# 8ModuleBoard.net
KiCad netlist of a schematic drawn in EAGLE
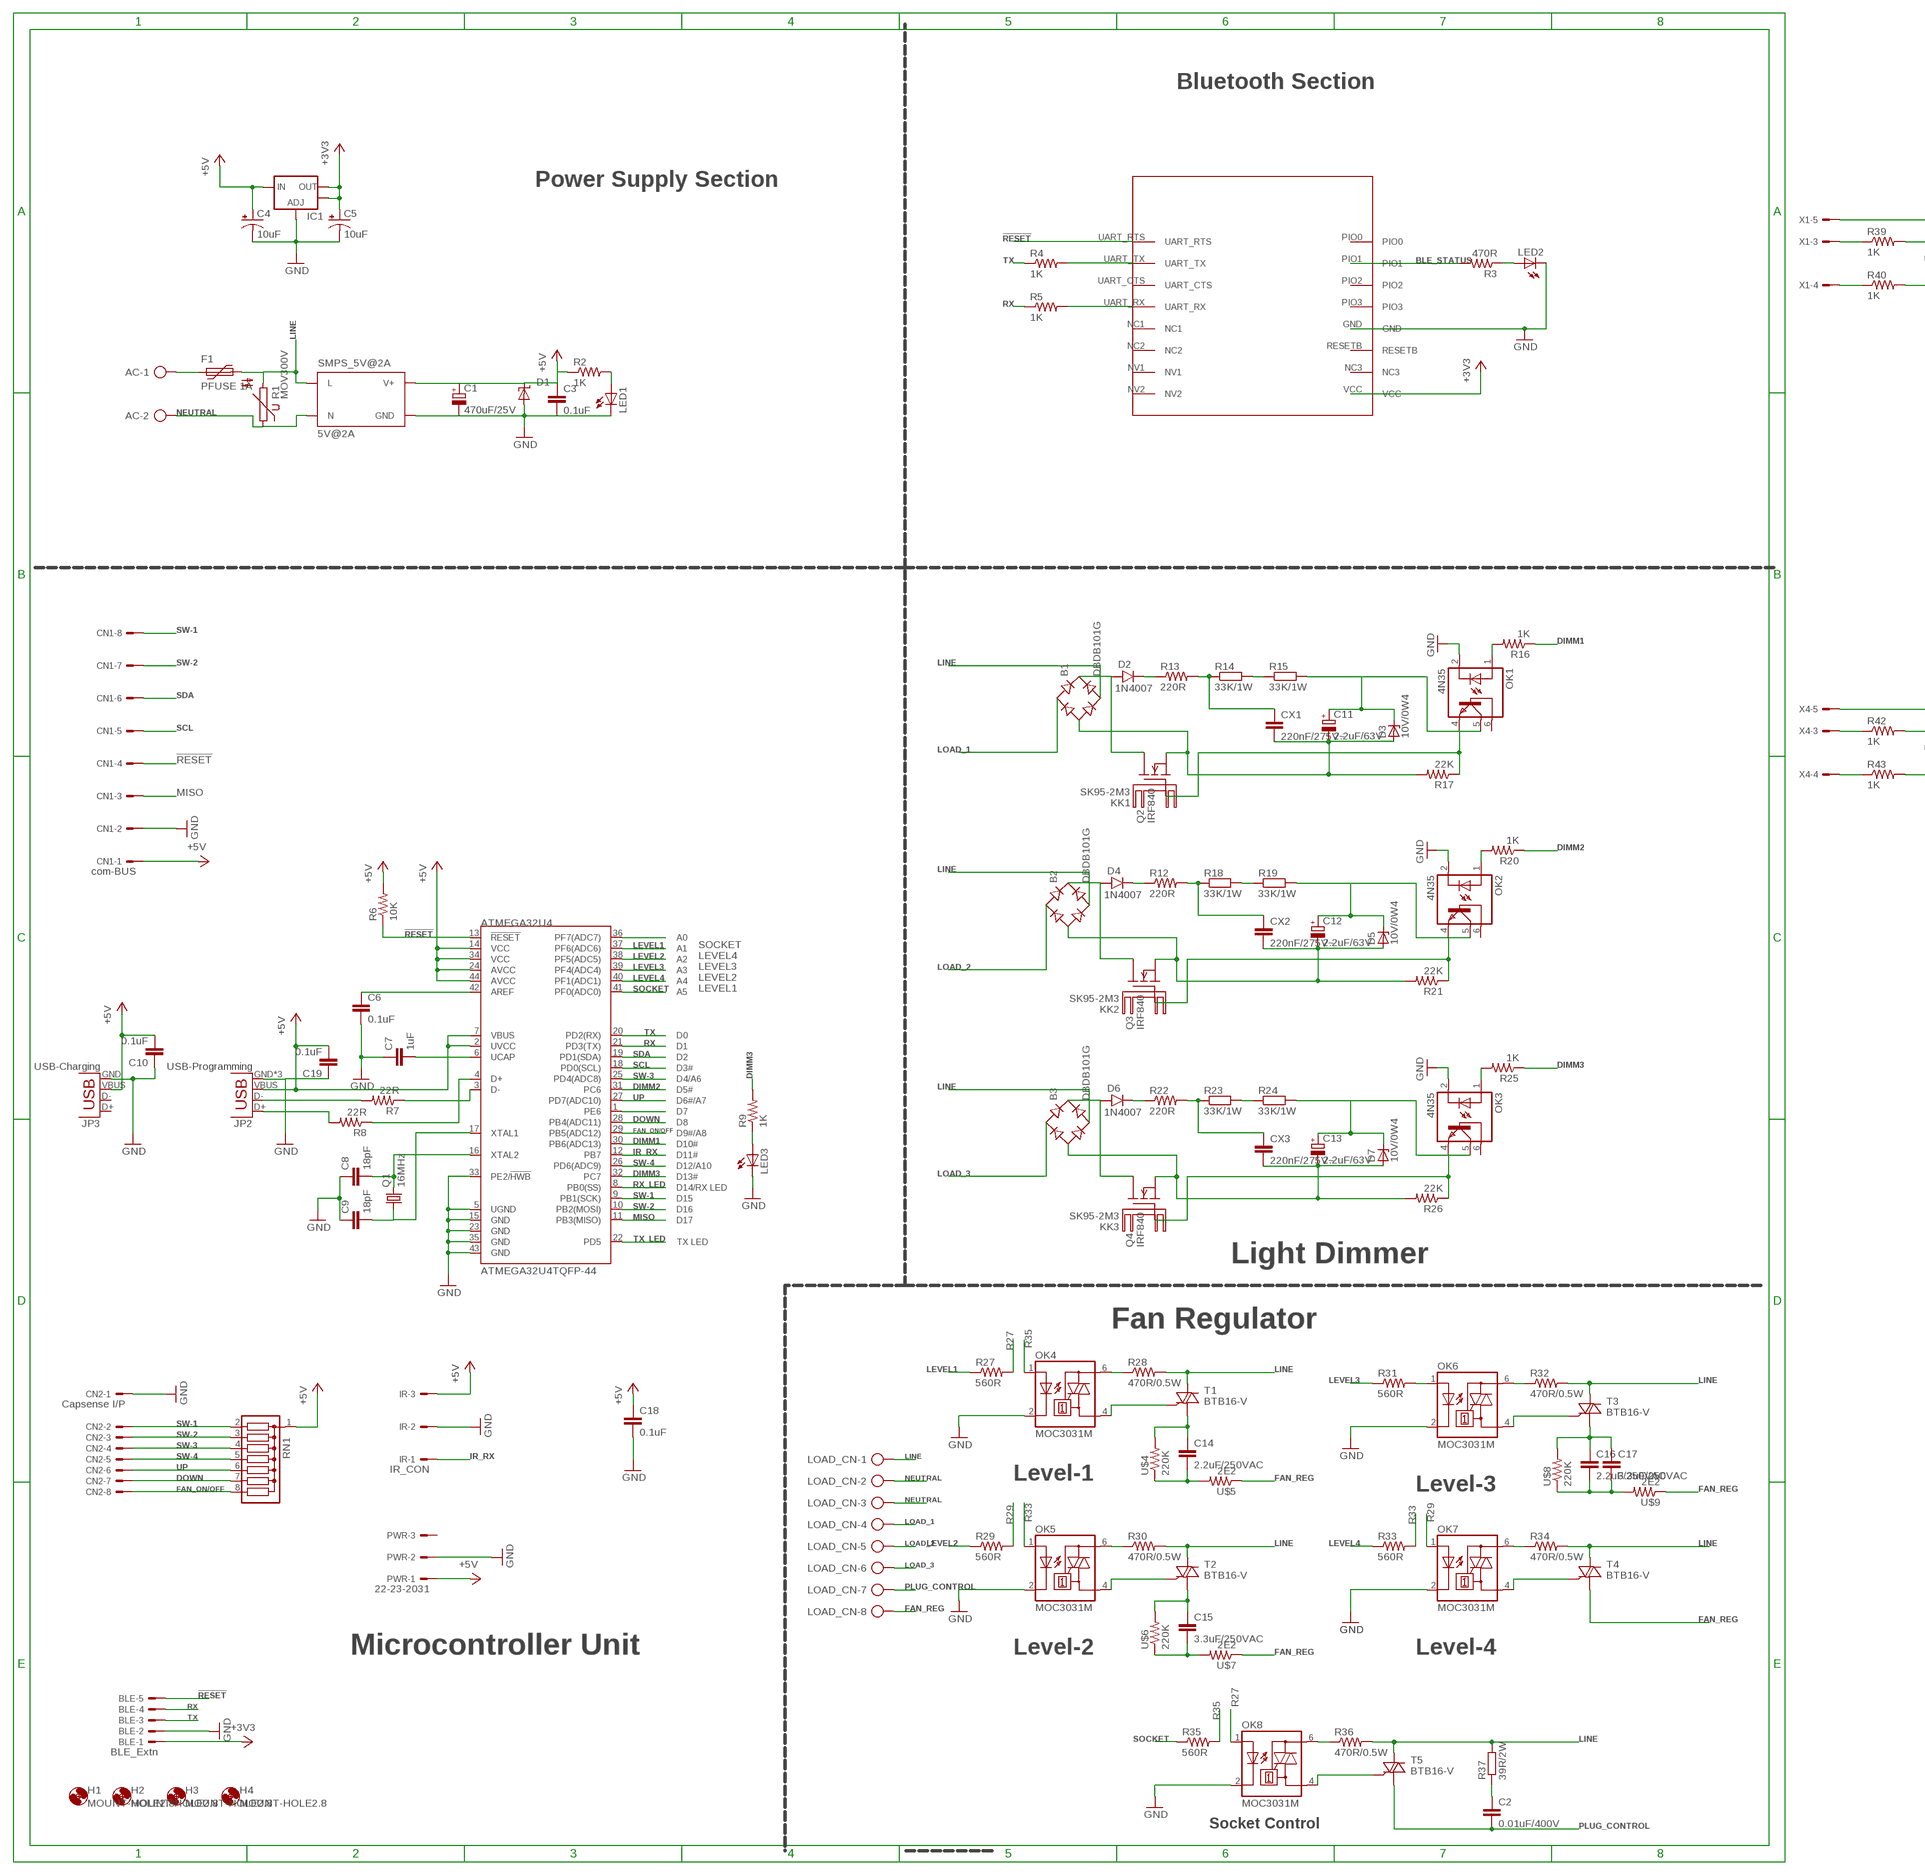
[diagram p0: schematic, sheet 1, part 1 of 2]
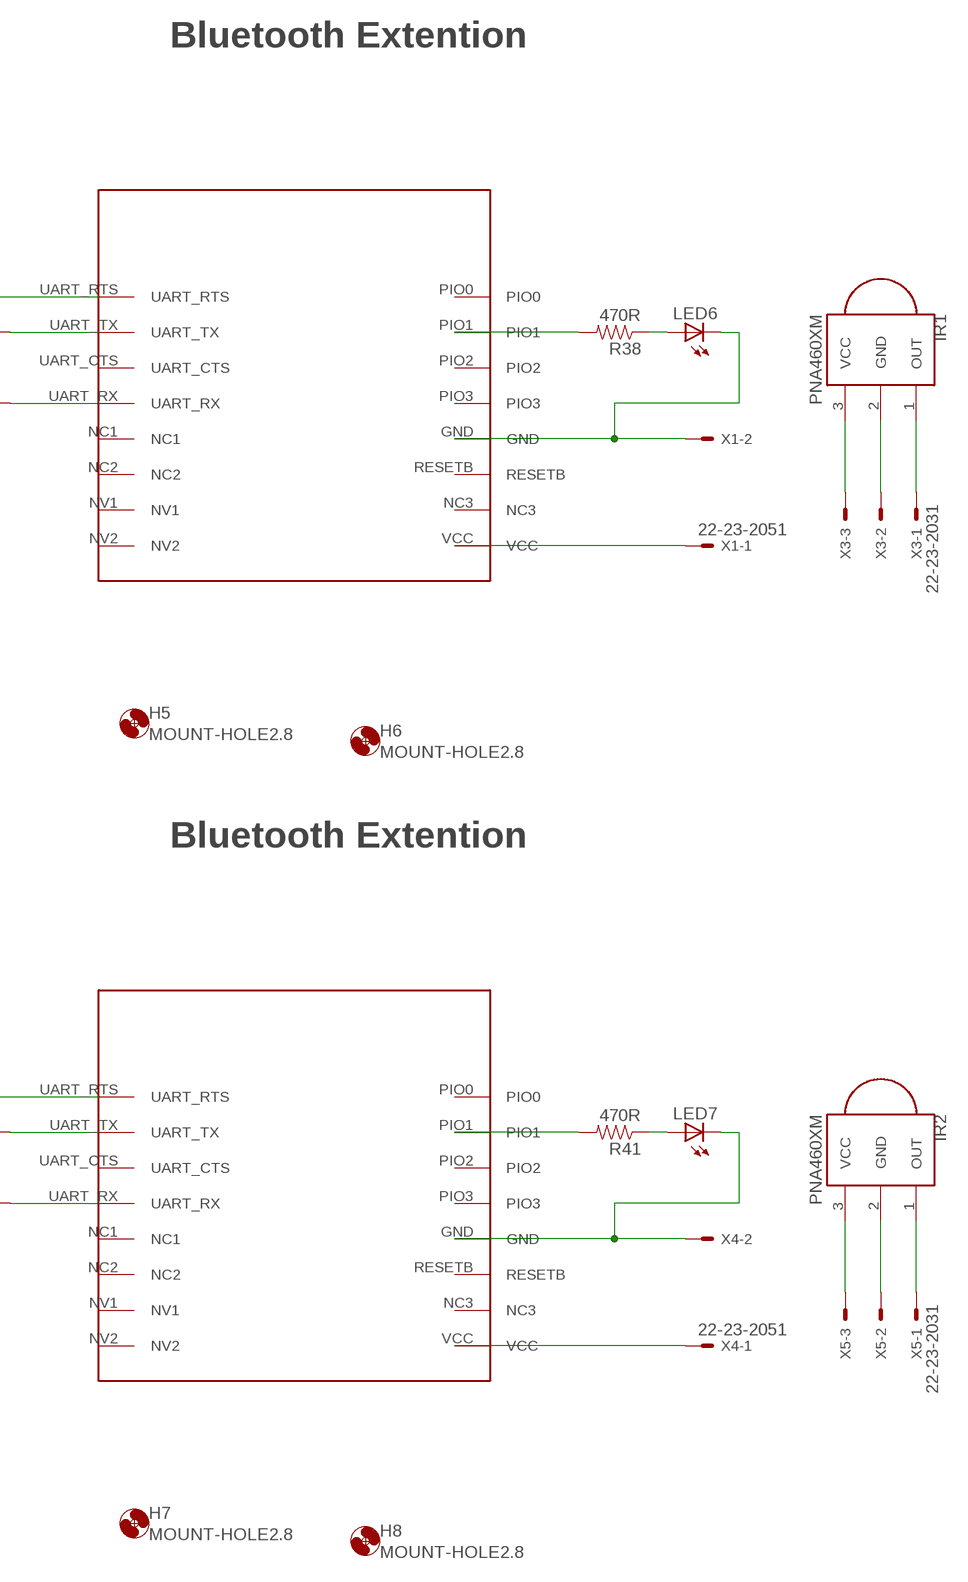
[diagram p1: schematic, sheet 1, part 2 of 2]

(export (version "E")
  (design (tool "Eeschema 10.0.6"))
  (components
    (comp (ref "AC")
      (value "AK300/2")
      (footprint "eagle-import:AK300_2")
      (libsource (lib "eagle-import") (part "AK300/2"))
    )
    (comp (ref "ATMEGA32U4")
      (value "ATMEGA32U4TQFP-44")
      (footprint "eagle-import:TQFP44")
      (libsource (lib "eagle-import") (part "ATMEGA32U4TQFP-44"))
    )
    (comp (ref "B1")
      (value "DBDB101G")
      (footprint "eagle-import:DB")
      (libsource (lib "eagle-import") (part "DB?GDB101"))
    )
    (comp (ref "B2")
      (value "DBDB101G")
      (footprint "eagle-import:DB")
      (libsource (lib "eagle-import") (part "DB?GDB101"))
    )
    (comp (ref "B3")
      (value "DBDB101G")
      (footprint "eagle-import:DB")
      (libsource (lib "eagle-import") (part "DB?GDB101"))
    )
    (comp (ref "BLE")
      (value "BLE_Extn")
      (footprint "eagle-import:22-23-2051")
      (fields (field (name "MF") "MOLEX") (field (name "MPN") "22-23-2051"))
      (libsource (lib "eagle-import") (part "22-23-2051"))
    )
    (comp (ref "C1")
      (value "470uF/25V")
      (footprint "eagle-import:E5-8,5")
      (libsource (lib "eagle-import") (part "CPOL-EUE5-8.5"))
    )
    (comp (ref "C2")
      (value "0.01uF/400V")
      (footprint "eagle-import:C2.5-2")
      (libsource (lib "eagle-import") (part "C2.5/2"))
    )
    (comp (ref "C3")
      (value "0.1uF")
      (footprint "eagle-import:1206")
      (libsource (lib "eagle-import") (part "1.0UF50V10%(1206)"))
    )
    (comp (ref "C4")
      (value "10uF")
      (footprint "eagle-import:EIA3216")
      (libsource (lib "eagle-import") (part "10UF-16V-10%(TANT)"))
    )
    (comp (ref "C5")
      (value "10uF")
      (footprint "eagle-import:EIA3216")
      (libsource (lib "eagle-import") (part "10UF-16V-10%(TANT)"))
    )
    (comp (ref "C6")
      (value "0.1uF")
      (footprint "eagle-import:1206")
      (libsource (lib "eagle-import") (part "CAP1206"))
    )
    (comp (ref "C7")
      (value "1uF")
      (footprint "eagle-import:1206")
      (libsource (lib "eagle-import") (part "CAP1206"))
    )
    (comp (ref "C8")
      (value "18pF")
      (footprint "eagle-import:1206")
      (libsource (lib "eagle-import") (part "CAP1206"))
    )
    (comp (ref "C9")
      (value "18pF")
      (footprint "eagle-import:1206")
      (libsource (lib "eagle-import") (part "CAP1206"))
    )
    (comp (ref "C10")
      (value "0.1uF")
      (footprint "eagle-import:1206")
      (libsource (lib "eagle-import") (part "CAP1206"))
    )
    (comp (ref "C11")
      (value "2.2uF/63V")
      (footprint "eagle-import:E1,8-4")
      (libsource (lib "eagle-import") (part "CPOL-EUE1.8-4"))
    )
    (comp (ref "C12")
      (value "2.2uF/63V")
      (footprint "eagle-import:E1,8-4")
      (libsource (lib "eagle-import") (part "CPOL-EUE1.8-4"))
    )
    (comp (ref "C13")
      (value "2.2uF/63V")
      (footprint "eagle-import:E1,8-4")
      (libsource (lib "eagle-import") (part "CPOL-EUE1.8-4"))
    )
    (comp (ref "C14")
      (value "2.2uF/250VAC")
      (footprint "eagle-import:C27.5B9")
      (libsource (lib "eagle-import") (part "C27/9"))
    )
    (comp (ref "C15")
      (value "3.3uF/250VAC")
      (footprint "eagle-import:C27.5B9")
      (libsource (lib "eagle-import") (part "C27/9"))
    )
    (comp (ref "C16")
      (value "2.2uF/250VAC")
      (footprint "eagle-import:C27.5B9")
      (libsource (lib "eagle-import") (part "C27/9"))
    )
    (comp (ref "C17")
      (value "3.3uF/250VAC")
      (footprint "eagle-import:C27.5B9")
      (libsource (lib "eagle-import") (part "C27/9"))
    )
    (comp (ref "C18")
      (value "0.1uF")
      (footprint "eagle-import:1206")
      (libsource (lib "eagle-import") (part "CAP1206"))
    )
    (comp (ref "C19")
      (value "0.1uF")
      (footprint "eagle-import:1206")
      (libsource (lib "eagle-import") (part "CAP1206"))
    )
    (comp (ref "CN1")
      (value "com-BUS")
      (footprint "eagle-import:22-23-2081")
      (fields (field (name "MF") "MOLEX") (field (name "MPN") "22-23-2081"))
      (libsource (lib "eagle-import") (part "22-23-2081"))
    )
    (comp (ref "CN2")
      (value "Capsense I/P")
      (footprint "eagle-import:22-23-2081")
      (fields (field (name "MF") "MOLEX") (field (name "MPN") "22-23-2081"))
      (libsource (lib "eagle-import") (part "22-23-2081"))
    )
    (comp (ref "CX1")
      (value "220nF/275V~")
      (footprint "eagle-import:XC15B5")
      (libsource (lib "eagle-import") (part "CXXC15B5"))
    )
    (comp (ref "CX2")
      (value "220nF/275V~")
      (footprint "eagle-import:XC15B5")
      (libsource (lib "eagle-import") (part "CXXC15B5"))
    )
    (comp (ref "CX3")
      (value "220nF/275V~")
      (footprint "eagle-import:XC15B5")
      (libsource (lib "eagle-import") (part "CXXC15B5"))
    )
    (comp (ref "D1")
      (value "SUPPRESSOR-SMBJ")
      (footprint "eagle-import:SMBJ")
      (libsource (lib "eagle-import") (part "SUPPRESSOR-SMBJ"))
    )
    (comp (ref "D2")
      (value "1N4007")
      (footprint "eagle-import:DO41-1")
      (libsource (lib "eagle-import") (part "1N400X.1"))
    )
    (comp (ref "D3")
      (value "10V/0W4")
      (footprint "eagle-import:ZDIO-2.5")
      (libsource (lib "eagle-import") (part "ZENER-DIODEZD-2.5"))
    )
    (comp (ref "D4")
      (value "1N4007")
      (footprint "eagle-import:DO41-1")
      (libsource (lib "eagle-import") (part "1N400X.1"))
    )
    (comp (ref "D5")
      (value "10V/0W4")
      (footprint "eagle-import:ZDIO-2.5")
      (libsource (lib "eagle-import") (part "ZENER-DIODEZD-2.5"))
    )
    (comp (ref "D6")
      (value "1N4007")
      (footprint "eagle-import:DO41-1")
      (libsource (lib "eagle-import") (part "1N400X.1"))
    )
    (comp (ref "D7")
      (value "10V/0W4")
      (footprint "eagle-import:ZDIO-2.5")
      (libsource (lib "eagle-import") (part "ZENER-DIODEZD-2.5"))
    )
    (comp (ref "F1")
      (value "PFUSE 1A")
      (footprint "eagle-import:MF-5,1B")
      (libsource (lib "eagle-import") (part "MF-R055-5,1B"))
    )
    (comp (ref "H1")
      (value "MOUNT-HOLE2.8")
      (footprint "eagle-import:2,8")
      (libsource (lib "eagle-import") (part "MOUNT-HOLE2.8"))
    )
    (comp (ref "H2")
      (value "MOUNT-HOLE2.8")
      (footprint "eagle-import:2,8")
      (libsource (lib "eagle-import") (part "MOUNT-HOLE2.8"))
    )
    (comp (ref "H3")
      (value "MOUNT-HOLE2.8")
      (footprint "eagle-import:2,8")
      (libsource (lib "eagle-import") (part "MOUNT-HOLE2.8"))
    )
    (comp (ref "H4")
      (value "MOUNT-HOLE2.8")
      (footprint "eagle-import:2,8")
      (libsource (lib "eagle-import") (part "MOUNT-HOLE2.8"))
    )
    (comp (ref "H5")
      (value "MOUNT-HOLE2.8")
      (footprint "eagle-import:2,8")
      (libsource (lib "eagle-import") (part "MOUNT-HOLE2.8"))
    )
    (comp (ref "H6")
      (value "MOUNT-HOLE2.8")
      (footprint "eagle-import:2,8")
      (libsource (lib "eagle-import") (part "MOUNT-HOLE2.8"))
    )
    (comp (ref "H7")
      (value "MOUNT-HOLE2.8")
      (footprint "eagle-import:2,8")
      (libsource (lib "eagle-import") (part "MOUNT-HOLE2.8"))
    )
    (comp (ref "H8")
      (value "MOUNT-HOLE2.8")
      (footprint "eagle-import:2,8")
      (libsource (lib "eagle-import") (part "MOUNT-HOLE2.8"))
    )
    (comp (ref "IC1")
      (value "V_REG_LM1117SOT223")
      (footprint "eagle-import:SOT223")
      (libsource (lib "eagle-import") (part "V_REG_LM1117SOT223"))
    )
    (comp (ref "IR")
      (value "IR_CON")
      (footprint "eagle-import:22-23-2031")
      (fields (field (name "MF") "MOLEX") (field (name "MPN") "22-23-2031"))
      (libsource (lib "eagle-import") (part "22-23-2031"))
    )
    (comp (ref "IR1")
      (value "PNA460XM")
      (footprint "eagle-import:PNA460XM")
      (libsource (lib "eagle-import") (part "PNA460XM"))
    )
    (comp (ref "IR2")
      (value "PNA460XM")
      (footprint "eagle-import:PNA460XM")
      (libsource (lib "eagle-import") (part "PNA460XM"))
    )
    (comp (ref "JP2")
      (value "USB-Programming")
      (footprint "eagle-import:USB-MICROB")
      (libsource (lib "eagle-import") (part "USB-MICROB"))
    )
    (comp (ref "JP3")
      (value "USB-Charging")
      (footprint "eagle-import:USB-A-H")
      (libsource (lib "eagle-import") (part "USB-A-H"))
    )
    (comp (ref "KK1")
      (value "SK95-2M3")
      (footprint "eagle-import:SK95-2M3")
      (libsource (lib "eagle-import") (part "SK95-2M3"))
    )
    (comp (ref "KK2")
      (value "SK95-2M3")
      (footprint "eagle-import:SK95-2M3")
      (libsource (lib "eagle-import") (part "SK95-2M3"))
    )
    (comp (ref "KK3")
      (value "SK95-2M3")
      (footprint "eagle-import:SK95-2M3")
      (libsource (lib "eagle-import") (part "SK95-2M3"))
    )
    (comp (ref "LED1")
      (value "LEDSML1206")
      (footprint "eagle-import:SML1206")
      (libsource (lib "eagle-import") (part "LEDSML1206"))
    )
    (comp (ref "LED2")
      (value "LEDSML1206")
      (footprint "eagle-import:SML1206")
      (libsource (lib "eagle-import") (part "LEDSML1206"))
    )
    (comp (ref "LED3")
      (value "LEDSML1206")
      (footprint "eagle-import:SML1206")
      (libsource (lib "eagle-import") (part "LEDSML1206"))
    )
    (comp (ref "LED6")
      (value "LEDSMT1206")
      (footprint "eagle-import:1206")
      (libsource (lib "eagle-import") (part "LEDSMT1206"))
    )
    (comp (ref "LED7")
      (value "LEDSMT1206")
      (footprint "eagle-import:1206")
      (libsource (lib "eagle-import") (part "LEDSMT1206"))
    )
    (comp (ref "LOAD_CN")
      (value "AK300/8")
      (footprint "eagle-import:AK300_8")
      (libsource (lib "eagle-import") (part "AK300/8"))
    )
    (comp (ref "OK1")
      (value "4N35")
      (footprint "eagle-import:DIL06")
      (fields (field (name "MF") "FAIRCHILD SEMICONDUCTOR"))
      (libsource (lib "eagle-import") (part "4N35"))
    )
    (comp (ref "OK2")
      (value "4N35")
      (footprint "eagle-import:DIL06")
      (fields (field (name "MF") "FAIRCHILD SEMICONDUCTOR"))
      (libsource (lib "eagle-import") (part "4N35"))
    )
    (comp (ref "OK3")
      (value "4N35")
      (footprint "eagle-import:DIL06")
      (fields (field (name "MF") "FAIRCHILD SEMICONDUCTOR"))
      (libsource (lib "eagle-import") (part "4N35"))
    )
    (comp (ref "OK4")
      (value "MOC3031M")
      (footprint "eagle-import:DIL06")
      (fields (field (name "MF") "FAIRCHILD SEMICONDUCTOR"))
      (libsource (lib "eagle-import") (part "MOC3031M"))
    )
    (comp (ref "OK5")
      (value "MOC3031M")
      (footprint "eagle-import:DIL06")
      (fields (field (name "MF") "FAIRCHILD SEMICONDUCTOR"))
      (libsource (lib "eagle-import") (part "MOC3031M"))
    )
    (comp (ref "OK6")
      (value "MOC3031M")
      (footprint "eagle-import:DIL06")
      (fields (field (name "MF") "FAIRCHILD SEMICONDUCTOR"))
      (libsource (lib "eagle-import") (part "MOC3031M"))
    )
    (comp (ref "OK7")
      (value "MOC3031M")
      (footprint "eagle-import:DIL06")
      (fields (field (name "MF") "FAIRCHILD SEMICONDUCTOR"))
      (libsource (lib "eagle-import") (part "MOC3031M"))
    )
    (comp (ref "OK8")
      (value "MOC3031M")
      (footprint "eagle-import:DIL06")
      (fields (field (name "MF") "FAIRCHILD SEMICONDUCTOR"))
      (libsource (lib "eagle-import") (part "MOC3031M"))
    )
    (comp (ref "PWR")
      (value "22-23-2031")
      (footprint "eagle-import:22-23-2031")
      (fields (field (name "MF") "MOLEX"))
      (libsource (lib "eagle-import") (part "22-23-2031"))
    )
    (comp (ref "Q1")
      (value "16MHz")
      (footprint "eagle-import:HC49UP")
      (libsource (lib "eagle-import") (part "CRYSTALHC49UP"))
    )
    (comp (ref "Q2")
      (value "IRF840")
      (footprint "eagle-import:TO220")
      (libsource (lib "eagle-import") (part "IRF840"))
    )
    (comp (ref "Q3")
      (value "IRF840")
      (footprint "eagle-import:TO220")
      (libsource (lib "eagle-import") (part "IRF840"))
    )
    (comp (ref "Q4")
      (value "IRF840")
      (footprint "eagle-import:TO220")
      (libsource (lib "eagle-import") (part "IRF840"))
    )
    (comp (ref "R1")
      (value "MOV300V")
      (footprint "eagle-import:S07K11")
      (libsource (lib "eagle-import") (part "S07K11"))
    )
    (comp (ref "R2")
      (value "1K")
      (footprint "eagle-import:1206")
      (libsource (lib "eagle-import") (part "SparkFun-Resistors_RESISTOR1206"))
    )
    (comp (ref "R3")
      (value "470R")
      (footprint "eagle-import:1206")
      (libsource (lib "eagle-import") (part "RESISTOR1206"))
    )
    (comp (ref "R4")
      (value "1K")
      (footprint "eagle-import:1206")
      (libsource (lib "eagle-import") (part "SparkFun-Resistors_RESISTOR1206"))
    )
    (comp (ref "R5")
      (value "1K")
      (footprint "eagle-import:1206")
      (libsource (lib "eagle-import") (part "SparkFun-Resistors_RESISTOR1206"))
    )
    (comp (ref "R6")
      (value "10K")
      (footprint "eagle-import:1206")
      (libsource (lib "eagle-import") (part "RESISTOR1206"))
    )
    (comp (ref "R7")
      (value "22R")
      (footprint "eagle-import:1206")
      (libsource (lib "eagle-import") (part "RESISTOR1206"))
    )
    (comp (ref "R8")
      (value "22R")
      (footprint "eagle-import:1206")
      (libsource (lib "eagle-import") (part "RESISTOR1206"))
    )
    (comp (ref "R9")
      (value "1K")
      (footprint "eagle-import:1206")
      (libsource (lib "eagle-import") (part "RESISTOR1206"))
    )
    (comp (ref "R12")
      (value "220R")
      (footprint "eagle-import:1206")
      (libsource (lib "eagle-import") (part "SparkFun-Resistors_RESISTOR1206"))
    )
    (comp (ref "R13")
      (value "220R")
      (footprint "eagle-import:1206")
      (libsource (lib "eagle-import") (part "SparkFun-Resistors_RESISTOR1206"))
    )
    (comp (ref "R14")
      (value "33K/1W")
      (footprint "eagle-import:0411V")
      (libsource (lib "eagle-import") (part "R-EU_0411/3V"))
    )
    (comp (ref "R15")
      (value "33K/1W")
      (footprint "eagle-import:0411V")
      (libsource (lib "eagle-import") (part "R-EU_0411/3V"))
    )
    (comp (ref "R16")
      (value "1K")
      (footprint "eagle-import:1206")
      (libsource (lib "eagle-import") (part "RESISTOR1206"))
    )
    (comp (ref "R17")
      (value "22K")
      (footprint "eagle-import:1206")
      (libsource (lib "eagle-import") (part "RESISTOR1206"))
    )
    (comp (ref "R18")
      (value "33K/1W")
      (footprint "eagle-import:0411V")
      (libsource (lib "eagle-import") (part "R-EU_0411/3V"))
    )
    (comp (ref "R19")
      (value "33K/1W")
      (footprint "eagle-import:0411V")
      (libsource (lib "eagle-import") (part "R-EU_0411/3V"))
    )
    (comp (ref "R20")
      (value "1K")
      (footprint "eagle-import:1206")
      (libsource (lib "eagle-import") (part "RESISTOR1206"))
    )
    (comp (ref "R21")
      (value "22K")
      (footprint "eagle-import:1206")
      (libsource (lib "eagle-import") (part "RESISTOR1206"))
    )
    (comp (ref "R22")
      (value "220R")
      (footprint "eagle-import:1206")
      (libsource (lib "eagle-import") (part "SparkFun-Resistors_RESISTOR1206"))
    )
    (comp (ref "R23")
      (value "33K/1W")
      (footprint "eagle-import:0411V")
      (libsource (lib "eagle-import") (part "R-EU_0411/3V"))
    )
    (comp (ref "R24")
      (value "33K/1W")
      (footprint "eagle-import:0411V")
      (libsource (lib "eagle-import") (part "R-EU_0411/3V"))
    )
    (comp (ref "R25")
      (value "1K")
      (footprint "eagle-import:1206")
      (libsource (lib "eagle-import") (part "RESISTOR1206"))
    )
    (comp (ref "R26")
      (value "22K")
      (footprint "eagle-import:1206")
      (libsource (lib "eagle-import") (part "RESISTOR1206"))
    )
    (comp (ref "R27")
      (value "560R")
      (footprint "eagle-import:1206")
      (libsource (lib "eagle-import") (part "SparkFun-Resistors_RESISTOR1206"))
    )
    (comp (ref "R28")
      (value "470R/0.5W")
      (footprint "eagle-import:0411V")
      (libsource (lib "eagle-import") (part "R-US_0411/3V"))
    )
    (comp (ref "R29")
      (value "560R")
      (footprint "eagle-import:1206")
      (libsource (lib "eagle-import") (part "SparkFun-Resistors_RESISTOR1206"))
    )
    (comp (ref "R30")
      (value "470R/0.5W")
      (footprint "eagle-import:0411V")
      (libsource (lib "eagle-import") (part "R-US_0411/3V"))
    )
    (comp (ref "R31")
      (value "560R")
      (footprint "eagle-import:1206")
      (libsource (lib "eagle-import") (part "SparkFun-Resistors_RESISTOR1206"))
    )
    (comp (ref "R32")
      (value "470R/0.5W")
      (footprint "eagle-import:0411V")
      (libsource (lib "eagle-import") (part "R-US_0411/3V"))
    )
    (comp (ref "R33")
      (value "560R")
      (footprint "eagle-import:1206")
      (libsource (lib "eagle-import") (part "SparkFun-Resistors_RESISTOR1206"))
    )
    (comp (ref "R34")
      (value "470R/0.5W")
      (footprint "eagle-import:0411V")
      (libsource (lib "eagle-import") (part "R-US_0411/3V"))
    )
    (comp (ref "R35")
      (value "560R")
      (footprint "eagle-import:1206")
      (libsource (lib "eagle-import") (part "SparkFun-Resistors_RESISTOR1206"))
    )
    (comp (ref "R36")
      (value "470R/0.5W")
      (footprint "eagle-import:0411V")
      (libsource (lib "eagle-import") (part "R-US_0411/3V"))
    )
    (comp (ref "R37")
      (value "39R/2W")
      (footprint "eagle-import:0411V")
      (libsource (lib "eagle-import") (part "R-EU_0411/3V"))
    )
    (comp (ref "R38")
      (value "470R")
      (footprint "eagle-import:1206")
      (libsource (lib "eagle-import") (part "RESISTOR1206"))
    )
    (comp (ref "R39")
      (value "1K")
      (footprint "eagle-import:1206")
      (libsource (lib "eagle-import") (part "SparkFun-Resistors_RESISTOR1206"))
    )
    (comp (ref "R40")
      (value "1K")
      (footprint "eagle-import:1206")
      (libsource (lib "eagle-import") (part "SparkFun-Resistors_RESISTOR1206"))
    )
    (comp (ref "R41")
      (value "470R")
      (footprint "eagle-import:1206")
      (libsource (lib "eagle-import") (part "RESISTOR1206"))
    )
    (comp (ref "R42")
      (value "1K")
      (footprint "eagle-import:1206")
      (libsource (lib "eagle-import") (part "SparkFun-Resistors_RESISTOR1206"))
    )
    (comp (ref "R43")
      (value "1K")
      (footprint "eagle-import:1206")
      (libsource (lib "eagle-import") (part "SparkFun-Resistors_RESISTOR1206"))
    )
    (comp (ref "RN1")
      (value "G07R")
      (footprint "eagle-import:SIL8")
      (libsource (lib "eagle-import") (part "G07R"))
    )
    (comp (ref "SMPS_5V@2A")
      (value "5V@2A")
      (footprint "eagle-import:MKS1854-6-0-404")
      (libsource (lib "eagle-import") (part "MKS1854-6-0-404"))
    )
    (comp (ref "T1")
      (value "BTB16-V")
      (footprint "eagle-import:TO220BV")
      (libsource (lib "eagle-import") (part "BT138-V"))
    )
    (comp (ref "T2")
      (value "BTB16-V")
      (footprint "eagle-import:TO220BV")
      (libsource (lib "eagle-import") (part "BT138-V"))
    )
    (comp (ref "T3")
      (value "BTB16-V")
      (footprint "eagle-import:TO220BV")
      (libsource (lib "eagle-import") (part "BT138-V"))
    )
    (comp (ref "T4")
      (value "BTB16-V")
      (footprint "eagle-import:TO220BV")
      (libsource (lib "eagle-import") (part "BT138-V"))
    )
    (comp (ref "T5")
      (value "BTB16-V")
      (footprint "eagle-import:TO220BV")
      (libsource (lib "eagle-import") (part "BT138-V"))
    )
    (comp (ref "U$1")
      (value "HM-11")
      (footprint "eagle-import:HM-11")
      (libsource (lib "eagle-import") (part "HM-11"))
    )
    (comp (ref "U$3")
      (value "HM-11")
      (footprint "eagle-import:HM-11")
      (libsource (lib "eagle-import") (part "HM-11"))
    )
    (comp (ref "U$4")
      (value "220K")
      (footprint "eagle-import:1206")
      (libsource (lib "eagle-import") (part "SparkFun-Resistors_RESISTOR1206"))
    )
    (comp (ref "U$5")
      (value "2E2")
      (footprint "eagle-import:1206")
      (libsource (lib "eagle-import") (part "SparkFun-Resistors_RESISTOR1206"))
    )
    (comp (ref "U$6")
      (value "220K")
      (footprint "eagle-import:1206")
      (libsource (lib "eagle-import") (part "SparkFun-Resistors_RESISTOR1206"))
    )
    (comp (ref "U$7")
      (value "2E2")
      (footprint "eagle-import:1206")
      (libsource (lib "eagle-import") (part "SparkFun-Resistors_RESISTOR1206"))
    )
    (comp (ref "U$8")
      (value "220K")
      (footprint "eagle-import:1206")
      (libsource (lib "eagle-import") (part "SparkFun-Resistors_RESISTOR1206"))
    )
    (comp (ref "U$9")
      (value "2E2")
      (footprint "eagle-import:1206")
      (libsource (lib "eagle-import") (part "SparkFun-Resistors_RESISTOR1206"))
    )
    (comp (ref "U$11")
      (value "HM-11")
      (footprint "eagle-import:HM-11")
      (libsource (lib "eagle-import") (part "HM-11"))
    )
    (comp (ref "X1")
      (value "22-23-2051")
      (footprint "eagle-import:22-23-2051")
      (fields (field (name "MF") "MOLEX"))
      (libsource (lib "eagle-import") (part "22-23-2051"))
    )
    (comp (ref "X3")
      (value "22-23-2031")
      (footprint "eagle-import:22-23-2031")
      (fields (field (name "MF") "MOLEX"))
      (libsource (lib "eagle-import") (part "22-23-2031"))
    )
    (comp (ref "X4")
      (value "22-23-2051")
      (footprint "eagle-import:22-23-2051")
      (fields (field (name "MF") "MOLEX"))
      (libsource (lib "eagle-import") (part "22-23-2051"))
    )
    (comp (ref "X5")
      (value "22-23-2031")
      (footprint "eagle-import:22-23-2031")
      (fields (field (name "MF") "MOLEX"))
      (libsource (lib "eagle-import") (part "22-23-2031"))
    )
  )
  (nets
    (net (code "1") (name "+3V3") (class "Default")
      (node (ref "BLE") (pin "1") (pinfunction "S_1") (pintype "passive"))
      (node (ref "C5") (pin "A") (pinfunction "+_A") (pintype "passive"))
      (node (ref "IC1") (pin "2") (pinfunction "OUT_2") (pintype "output"))
      (node (ref "IC1") (pin "4") (pinfunction "OUT_4") (pintype "output"))
      (node (ref "U$3") (pin "VCC") (pinfunction "VCC_VCC") (pintype "bidirectional"))
    )
    (net (code "2") (name "+5V") (class "Default")
      (node (ref "ATMEGA32U4") (pin "14") (pinfunction "VCC_14") (pintype "bidirectional"))
      (node (ref "ATMEGA32U4") (pin "2") (pinfunction "UVCC_2") (pintype "bidirectional"))
      (node (ref "ATMEGA32U4") (pin "24") (pinfunction "AVCC_24") (pintype "bidirectional"))
      (node (ref "ATMEGA32U4") (pin "34") (pinfunction "VCC_34") (pintype "bidirectional"))
      (node (ref "ATMEGA32U4") (pin "44") (pinfunction "AVCC_44") (pintype "bidirectional"))
      (node (ref "ATMEGA32U4") (pin "7") (pinfunction "VBUS_7") (pintype "bidirectional"))
      (node (ref "C1") (pin "+") (pinfunction "+_+") (pintype "passive"))
      (node (ref "C10") (pin "2") (pinfunction "2_2") (pintype "passive"))
      (node (ref "C18") (pin "1") (pinfunction "1_1") (pintype "passive"))
      (node (ref "C19") (pin "2") (pinfunction "2_2") (pintype "passive"))
      (node (ref "C3") (pin "1") (pinfunction "1_1") (pintype "passive"))
      (node (ref "C4") (pin "A") (pinfunction "+_A") (pintype "passive"))
      (node (ref "CN1") (pin "1") (pinfunction "S_1") (pintype "passive"))
      (node (ref "D1") (pin "C") (pinfunction "C_C") (pintype "passive"))
      (node (ref "IC1") (pin "3") (pinfunction "IN_3") (pintype "input"))
      (node (ref "IR") (pin "3") (pinfunction "S_3") (pintype "passive"))
      (node (ref "JP2") (pin "VBUS") (pinfunction "VBUS_VBUS") (pintype "bidirectional"))
      (node (ref "JP3") (pin "VBUS") (pinfunction "VBUS_VBUS") (pintype "bidirectional"))
      (node (ref "PWR") (pin "1") (pinfunction "S_1") (pintype "passive"))
      (node (ref "R2") (pin "1") (pinfunction "1_1") (pintype "passive"))
      (node (ref "R6") (pin "2") (pinfunction "2_2") (pintype "passive"))
      (node (ref "RN1") (pin "1") (pinfunction "1_1") (pintype "passive"))
      (node (ref "SMPS_5V@2A") (pin "3") (pinfunction "V+_3") (pintype "input"))
    )
    (net (code "3") (name "/BGND") (class "Default")
      (node (ref "IR1") (pin "2") (pinfunction "GND_2") (pintype "power_in"))
      (node (ref "LED6") (pin "C") (pinfunction "C_C") (pintype "passive"))
      (node (ref "U$1") (pin "GND") (pinfunction "GND_GND") (pintype "bidirectional"))
      (node (ref "X1") (pin "2") (pinfunction "S_2") (pintype "passive"))
      (node (ref "X3") (pin "2") (pinfunction "S_2") (pintype "passive"))
    )
    (net (code "4") (name "/BLE_STATUS") (class "Default")
      (node (ref "R3") (pin "2") (pinfunction "2_2") (pintype "passive"))
      (node (ref "U$3") (pin "PIO1") (pinfunction "PIO1_PIO1") (pintype "bidirectional"))
    )
    (net (code "5") (name "/CGND") (class "Default")
      (node (ref "IR2") (pin "2") (pinfunction "GND_2") (pintype "power_in"))
      (node (ref "LED7") (pin "C") (pinfunction "C_C") (pintype "passive"))
      (node (ref "U$11") (pin "GND") (pinfunction "GND_GND") (pintype "bidirectional"))
      (node (ref "X4") (pin "2") (pinfunction "S_2") (pintype "passive"))
      (node (ref "X5") (pin "2") (pinfunction "S_2") (pintype "passive"))
    )
    (net (code "6") (name "/DIMM1") (class "Default")
      (node (ref "ATMEGA32U4") (pin "30") (pinfunction "PB6(ADC13)_30") (pintype "bidirectional"))
      (node (ref "R16") (pin "1") (pinfunction "1_1") (pintype "passive"))
    )
    (net (code "7") (name "/DIMM2") (class "Default")
      (node (ref "ATMEGA32U4") (pin "31") (pinfunction "PC6_31") (pintype "bidirectional"))
      (node (ref "R20") (pin "1") (pinfunction "1_1") (pintype "passive"))
    )
    (net (code "8") (name "/DIMM3") (class "Default")
      (node (ref "ATMEGA32U4") (pin "32") (pinfunction "PC7_32") (pintype "bidirectional"))
      (node (ref "R25") (pin "1") (pinfunction "1_1") (pintype "passive"))
      (node (ref "R9") (pin "2") (pinfunction "2_2") (pintype "passive"))
    )
    (net (code "9") (name "/DOWN") (class "Default")
      (node (ref "ATMEGA32U4") (pin "28") (pinfunction "PB4(ADC11)_28") (pintype "bidirectional"))
      (node (ref "CN2") (pin "7") (pinfunction "S_7") (pintype "passive"))
      (node (ref "RN1") (pin "7") (pinfunction "7_7") (pintype "passive"))
    )
    (net (code "10") (name "/FAN_ON{slash}OFF") (class "Default")
      (node (ref "ATMEGA32U4") (pin "29") (pinfunction "PB5(ADC12)_29") (pintype "bidirectional"))
      (node (ref "CN2") (pin "8") (pinfunction "S_8") (pintype "passive"))
      (node (ref "RN1") (pin "8") (pinfunction "8_8") (pintype "passive"))
    )
    (net (code "11") (name "/FAN_REG") (class "Default")
      (node (ref "LOAD_CN") (pin "8") (pinfunction "KL_8") (pintype "passive"))
      (node (ref "T4") (pin "T1") (pinfunction "A1_T1") (pintype "passive"))
      (node (ref "U$5") (pin "1") (pinfunction "1_1") (pintype "passive"))
      (node (ref "U$7") (pin "1") (pinfunction "1_1") (pintype "passive"))
      (node (ref "U$9") (pin "1") (pinfunction "1_1") (pintype "passive"))
    )
    (net (code "12") (name "/IR_RX") (class "Default")
      (node (ref "ATMEGA32U4") (pin "12") (pinfunction "PB7_12") (pintype "bidirectional"))
      (node (ref "IR") (pin "1") (pinfunction "S_1") (pintype "passive"))
    )
    (net (code "13") (name "/LEVEL1") (class "Default")
      (node (ref "ATMEGA32U4") (pin "37") (pinfunction "PF6(ADC6)_37") (pintype "bidirectional"))
      (node (ref "R27") (pin "1") (pinfunction "1_1") (pintype "passive"))
    )
    (net (code "14") (name "/LEVEL2") (class "Default")
      (node (ref "ATMEGA32U4") (pin "38") (pinfunction "PF5(ADC5)_38") (pintype "bidirectional"))
      (node (ref "R29") (pin "1") (pinfunction "1_1") (pintype "passive"))
    )
    (net (code "15") (name "/LEVEL3") (class "Default")
      (node (ref "ATMEGA32U4") (pin "39") (pinfunction "PF4(ADC4)_39") (pintype "bidirectional"))
      (node (ref "R31") (pin "1") (pinfunction "1_1") (pintype "passive"))
    )
    (net (code "16") (name "/LEVEL4") (class "Default")
      (node (ref "ATMEGA32U4") (pin "40") (pinfunction "PF1(ADC1)_40") (pintype "bidirectional"))
      (node (ref "R33") (pin "1") (pinfunction "1_1") (pintype "passive"))
    )
    (net (code "17") (name "/LINE") (class "Default")
      (node (ref "B1") (pin "AC2") (pinfunction "AC2_AC2") (pintype "passive"))
      (node (ref "B2") (pin "AC2") (pinfunction "AC2_AC2") (pintype "passive"))
      (node (ref "B3") (pin "AC2") (pinfunction "AC2_AC2") (pintype "passive"))
      (node (ref "F1") (pin "2") (pinfunction "2_2") (pintype "passive"))
      (node (ref "LOAD_CN") (pin "1") (pinfunction "KL_1") (pintype "passive"))
      (node (ref "R1") (pin "2") (pinfunction "2_2") (pintype "passive"))
      (node (ref "R28") (pin "2") (pinfunction "2_2") (pintype "passive"))
      (node (ref "R30") (pin "2") (pinfunction "2_2") (pintype "passive"))
      (node (ref "R32") (pin "2") (pinfunction "2_2") (pintype "passive"))
      (node (ref "R34") (pin "2") (pinfunction "2_2") (pintype "passive"))
      (node (ref "R36") (pin "2") (pinfunction "2_2") (pintype "passive"))
      (node (ref "R37") (pin "2") (pinfunction "2_2") (pintype "passive"))
      (node (ref "SMPS_5V@2A") (pin "1") (pinfunction "L_1") (pintype "input"))
      (node (ref "T1") (pin "T2") (pinfunction "A2_T2") (pintype "passive"))
      (node (ref "T2") (pin "T2") (pinfunction "A2_T2") (pintype "passive"))
      (node (ref "T3") (pin "T2") (pinfunction "A2_T2") (pintype "passive"))
      (node (ref "T4") (pin "T2") (pinfunction "A2_T2") (pintype "passive"))
      (node (ref "T5") (pin "T2") (pinfunction "A2_T2") (pintype "passive"))
    )
    (net (code "18") (name "/LOAD_1") (class "Default")
      (node (ref "B1") (pin "AC1") (pinfunction "AC1_AC1") (pintype "passive"))
      (node (ref "LOAD_CN") (pin "4") (pinfunction "KL_4") (pintype "passive"))
    )
    (net (code "19") (name "/LOAD_2") (class "Default")
      (node (ref "B2") (pin "AC1") (pinfunction "AC1_AC1") (pintype "passive"))
      (node (ref "LOAD_CN") (pin "5") (pinfunction "KL_5") (pintype "passive"))
    )
    (net (code "20") (name "/LOAD_3") (class "Default")
      (node (ref "B3") (pin "AC1") (pinfunction "AC1_AC1") (pintype "passive"))
      (node (ref "LOAD_CN") (pin "6") (pinfunction "KL_6") (pintype "passive"))
    )
    (net (code "21") (name "/MISO") (class "Default")
      (node (ref "ATMEGA32U4") (pin "11") (pinfunction "PB3(MISO)_11") (pintype "bidirectional"))
      (node (ref "CN1") (pin "3") (pinfunction "S_3") (pintype "passive"))
    )
    (net (code "22") (name "/NEUTRAL") (class "Default")
      (node (ref "AC") (pin "2") (pinfunction "KL_2") (pintype "passive"))
      (node (ref "LOAD_CN") (pin "2") (pinfunction "KL_2") (pintype "passive"))
      (node (ref "LOAD_CN") (pin "3") (pinfunction "KL_3") (pintype "passive"))
      (node (ref "R1") (pin "1") (pinfunction "1_1") (pintype "passive"))
      (node (ref "SMPS_5V@2A") (pin "2") (pinfunction "N_2") (pintype "input"))
    )
    (net (code "23") (name "/PLUG_CONTROL") (class "Default")
      (node (ref "C2") (pin "2") (pinfunction "2_2") (pintype "passive"))
      (node (ref "LOAD_CN") (pin "7") (pinfunction "KL_7") (pintype "passive"))
      (node (ref "T5") (pin "T1") (pinfunction "A1_T1") (pintype "passive"))
    )
    (net (code "24") (name "/R27") (class "Default")
      (node (ref "OK8") (pin "1") (pinfunction "A_1") (pintype "passive"))
      (node (ref "R27") (pin "2") (pinfunction "2_2") (pintype "passive"))
    )
    (net (code "25") (name "/R29") (class "Default")
      (node (ref "OK7") (pin "1") (pinfunction "A_1") (pintype "passive"))
      (node (ref "R29") (pin "2") (pinfunction "2_2") (pintype "passive"))
    )
    (net (code "26") (name "/R33") (class "Default")
      (node (ref "OK5") (pin "1") (pinfunction "A_1") (pintype "passive"))
      (node (ref "R33") (pin "2") (pinfunction "2_2") (pintype "passive"))
    )
    (net (code "27") (name "/R35") (class "Default")
      (node (ref "OK4") (pin "1") (pinfunction "A_1") (pintype "passive"))
      (node (ref "R35") (pin "2") (pinfunction "2_2") (pintype "passive"))
    )
    (net (code "28") (name "/RX") (class "Default")
      (node (ref "ATMEGA32U4") (pin "21") (pinfunction "PD3(TX)_21") (pintype "bidirectional"))
      (node (ref "BLE") (pin "4") (pinfunction "S_4") (pintype "passive"))
      (node (ref "R5") (pin "1") (pinfunction "1_1") (pintype "passive"))
    )
    (net (code "29") (name "/RX_LED") (class "Default")
      (node (ref "ATMEGA32U4") (pin "8") (pinfunction "PB0(SS)_8") (pintype "bidirectional"))
    )
    (net (code "30") (name "/SCL") (class "Default")
      (node (ref "ATMEGA32U4") (pin "18") (pinfunction "PD0(SCL)_18") (pintype "bidirectional"))
      (node (ref "CN1") (pin "5") (pinfunction "S_5") (pintype "passive"))
    )
    (net (code "31") (name "/SDA") (class "Default")
      (node (ref "ATMEGA32U4") (pin "19") (pinfunction "PD1(SDA)_19") (pintype "bidirectional"))
      (node (ref "CN1") (pin "6") (pinfunction "S_6") (pintype "passive"))
    )
    (net (code "32") (name "/SOCKET") (class "Default")
      (node (ref "ATMEGA32U4") (pin "41") (pinfunction "PF0(ADC0)_41") (pintype "bidirectional"))
      (node (ref "R35") (pin "1") (pinfunction "1_1") (pintype "passive"))
    )
    (net (code "33") (name "/SW-1") (class "Default")
      (node (ref "ATMEGA32U4") (pin "9") (pinfunction "PB1(SCK)_9") (pintype "bidirectional"))
      (node (ref "CN1") (pin "8") (pinfunction "S_8") (pintype "passive"))
      (node (ref "CN2") (pin "2") (pinfunction "S_2") (pintype "passive"))
      (node (ref "RN1") (pin "2") (pinfunction "2_2") (pintype "passive"))
    )
    (net (code "34") (name "/SW-2") (class "Default")
      (node (ref "ATMEGA32U4") (pin "10") (pinfunction "PB2(MOSI)_10") (pintype "bidirectional"))
      (node (ref "CN1") (pin "7") (pinfunction "S_7") (pintype "passive"))
      (node (ref "CN2") (pin "3") (pinfunction "S_3") (pintype "passive"))
      (node (ref "RN1") (pin "3") (pinfunction "3_3") (pintype "passive"))
    )
    (net (code "35") (name "/SW-3") (class "Default")
      (node (ref "ATMEGA32U4") (pin "25") (pinfunction "PD4(ADC8)_25") (pintype "bidirectional"))
      (node (ref "CN2") (pin "4") (pinfunction "S_4") (pintype "passive"))
      (node (ref "RN1") (pin "4") (pinfunction "4_4") (pintype "passive"))
    )
    (net (code "36") (name "/SW-4") (class "Default")
      (node (ref "ATMEGA32U4") (pin "26") (pinfunction "PD6(ADC9)_26") (pintype "bidirectional"))
      (node (ref "CN2") (pin "5") (pinfunction "S_5") (pintype "passive"))
      (node (ref "RN1") (pin "5") (pinfunction "5_5") (pintype "passive"))
    )
    (net (code "37") (name "/TX") (class "Default")
      (node (ref "ATMEGA32U4") (pin "20") (pinfunction "PD2(RX)_20") (pintype "bidirectional"))
      (node (ref "BLE") (pin "3") (pinfunction "S_3") (pintype "passive"))
      (node (ref "R4") (pin "1") (pinfunction "1_1") (pintype "passive"))
    )
    (net (code "38") (name "/TX_LED") (class "Default")
      (node (ref "ATMEGA32U4") (pin "22") (pinfunction "PD5_22") (pintype "bidirectional"))
    )
    (net (code "39") (name "/UP") (class "Default")
      (node (ref "ATMEGA32U4") (pin "27") (pinfunction "PD7(ADC10)_27") (pintype "bidirectional"))
      (node (ref "CN2") (pin "6") (pinfunction "S_6") (pintype "passive"))
      (node (ref "RN1") (pin "6") (pinfunction "6_6") (pintype "passive"))
    )
    (net (code "40") (name "/~{RESET}") (class "Default")
      (node (ref "ATMEGA32U4") (pin "13") (pinfunction "~{RESET}_13") (pintype "bidirectional"))
      (node (ref "BLE") (pin "5") (pinfunction "S_5") (pintype "passive"))
      (node (ref "CN1") (pin "4") (pinfunction "S_4") (pintype "passive"))
      (node (ref "R6") (pin "1") (pinfunction "1_1") (pintype "passive"))
      (node (ref "U$3") (pin "UART_RTS") (pinfunction "UART_RTS_UART_RTS") (pintype "bidirectional"))
    )
    (net (code "41") (name "GND") (class "Default")
      (node (ref "ATMEGA32U4") (pin "15") (pinfunction "GND_15") (pintype "bidirectional"))
      (node (ref "ATMEGA32U4") (pin "23") (pinfunction "GND_23") (pintype "bidirectional"))
      (node (ref "ATMEGA32U4") (pin "33") (pinfunction "PE2/~{HWB}_33") (pintype "bidirectional"))
      (node (ref "ATMEGA32U4") (pin "35") (pinfunction "GND_35") (pintype "bidirectional"))
      (node (ref "ATMEGA32U4") (pin "43") (pinfunction "GND_43") (pintype "bidirectional"))
      (node (ref "ATMEGA32U4") (pin "5") (pinfunction "UGND_5") (pintype "bidirectional"))
      (node (ref "BLE") (pin "2") (pinfunction "S_2") (pintype "passive"))
      (node (ref "C1") (pin "-") (pinfunction "-_-") (pintype "passive"))
      (node (ref "C10") (pin "1") (pinfunction "1_1") (pintype "passive"))
      (node (ref "C18") (pin "2") (pinfunction "2_2") (pintype "passive"))
      (node (ref "C19") (pin "1") (pinfunction "1_1") (pintype "passive"))
      (node (ref "C3") (pin "2") (pinfunction "2_2") (pintype "passive"))
      (node (ref "C4") (pin "C") (pinfunction "-_C") (pintype "passive"))
      (node (ref "C5") (pin "C") (pinfunction "-_C") (pintype "passive"))
      (node (ref "C6") (pin "2") (pinfunction "2_2") (pintype "passive"))
      (node (ref "C7") (pin "1") (pinfunction "1_1") (pintype "passive"))
      (node (ref "C8") (pin "1") (pinfunction "1_1") (pintype "passive"))
      (node (ref "C9") (pin "1") (pinfunction "1_1") (pintype "passive"))
      (node (ref "CN1") (pin "2") (pinfunction "S_2") (pintype "passive"))
      (node (ref "CN2") (pin "1") (pinfunction "S_1") (pintype "passive"))
      (node (ref "D1") (pin "A") (pinfunction "A_A") (pintype "passive"))
      (node (ref "IC1") (pin "1") (pinfunction "ADJ_1") (pintype "input"))
      (node (ref "IR") (pin "2") (pinfunction "S_2") (pintype "passive"))
      (node (ref "JP2") (pin "GND") (pinfunction "GND_GND") (pintype "bidirectional"))
      (node (ref "JP2") (pin "MT1") (pinfunction "GND_MT1") (pintype "bidirectional"))
      (node (ref "JP2") (pin "MT2") (pinfunction "GND_MT2") (pintype "bidirectional"))
      (node (ref "JP3") (pin "GND") (pinfunction "GND_GND") (pintype "bidirectional"))
      (node (ref "LED1") (pin "C") (pinfunction "C_C") (pintype "passive"))
      (node (ref "LED2") (pin "C") (pinfunction "C_C") (pintype "passive"))
      (node (ref "LED3") (pin "C") (pinfunction "C_C") (pintype "passive"))
      (node (ref "OK1") (pin "2") (pinfunction "C_2") (pintype "passive"))
      (node (ref "OK2") (pin "2") (pinfunction "C_2") (pintype "passive"))
      (node (ref "OK3") (pin "2") (pinfunction "C_2") (pintype "passive"))
      (node (ref "OK4") (pin "2") (pinfunction "C_2") (pintype "passive"))
      (node (ref "OK5") (pin "2") (pinfunction "C_2") (pintype "passive"))
      (node (ref "OK6") (pin "2") (pinfunction "C_2") (pintype "passive"))
      (node (ref "OK7") (pin "2") (pinfunction "C_2") (pintype "passive"))
      (node (ref "OK8") (pin "2") (pinfunction "C_2") (pintype "passive"))
      (node (ref "PWR") (pin "2") (pinfunction "S_2") (pintype "passive"))
      (node (ref "SMPS_5V@2A") (pin "4") (pinfunction "GND_4") (pintype "input"))
      (node (ref "U$3") (pin "GND") (pinfunction "GND_GND") (pintype "bidirectional"))
    )
    (net (code "42") (name "Net-(ACA-KL)") (class "Default")
      (node (ref "AC") (pin "1") (pinfunction "KL_1") (pintype "passive"))
      (node (ref "F1") (pin "1") (pinfunction "1_1") (pintype "passive"))
    )
    (net (code "43") (name "Net-(ATMEGA32U4-AREF)") (class "Default")
      (node (ref "ATMEGA32U4") (pin "42") (pinfunction "AREF_42") (pintype "bidirectional"))
      (node (ref "C6") (pin "1") (pinfunction "1_1") (pintype "passive"))
    )
    (net (code "44") (name "Net-(ATMEGA32U4-D+)") (class "Default")
      (node (ref "ATMEGA32U4") (pin "4") (pinfunction "D+_4") (pintype "bidirectional"))
      (node (ref "R8") (pin "1") (pinfunction "1_1") (pintype "passive"))
    )
    (net (code "45") (name "Net-(ATMEGA32U4-D-)") (class "Default")
      (node (ref "ATMEGA32U4") (pin "3") (pinfunction "D-_3") (pintype "bidirectional"))
      (node (ref "R7") (pin "1") (pinfunction "1_1") (pintype "passive"))
    )
    (net (code "46") (name "Net-(ATMEGA32U4-UCAP)") (class "Default")
      (node (ref "ATMEGA32U4") (pin "6") (pinfunction "UCAP_6") (pintype "bidirectional"))
      (node (ref "C7") (pin "2") (pinfunction "2_2") (pintype "passive"))
    )
    (net (code "47") (name "Net-(ATMEGA32U4-XTAL1)") (class "Default")
      (node (ref "ATMEGA32U4") (pin "17") (pinfunction "XTAL1_17") (pintype "bidirectional"))
      (node (ref "C9") (pin "2") (pinfunction "2_2") (pintype "passive"))
      (node (ref "Q1") (pin "1") (pinfunction "1_1") (pintype "passive"))
    )
    (net (code "48") (name "Net-(ATMEGA32U4-XTAL2)") (class "Default")
      (node (ref "ATMEGA32U4") (pin "16") (pinfunction "XTAL2_16") (pintype "bidirectional"))
      (node (ref "C8") (pin "2") (pinfunction "2_2") (pintype "passive"))
      (node (ref "Q1") (pin "2") (pinfunction "2_2") (pintype "passive"))
    )
    (net (code "49") (name "Net-(C2-Pad1)") (class "Default")
      (node (ref "C2") (pin "1") (pinfunction "1_1") (pintype "passive"))
      (node (ref "R37") (pin "1") (pinfunction "1_1") (pintype "passive"))
    )
    (net (code "50") (name "Net-(C14-Pad2)") (class "Default")
      (node (ref "C14") (pin "2") (pinfunction "2_2") (pintype "passive"))
      (node (ref "U$4") (pin "1") (pinfunction "1_1") (pintype "passive"))
      (node (ref "U$5") (pin "2") (pinfunction "2_2") (pintype "passive"))
    )
    (net (code "51") (name "Net-(C15-Pad2)") (class "Default")
      (node (ref "C15") (pin "2") (pinfunction "2_2") (pintype "passive"))
      (node (ref "U$6") (pin "1") (pinfunction "1_1") (pintype "passive"))
      (node (ref "U$7") (pin "2") (pinfunction "2_2") (pintype "passive"))
    )
    (net (code "52") (name "Net-(C16-Pad2)") (class "Default")
      (node (ref "C16") (pin "2") (pinfunction "2_2") (pintype "passive"))
      (node (ref "C17") (pin "2") (pinfunction "2_2") (pintype "passive"))
      (node (ref "U$8") (pin "1") (pinfunction "1_1") (pintype "passive"))
      (node (ref "U$9") (pin "2") (pinfunction "2_2") (pintype "passive"))
    )
    (net (code "53") (name "Net-(CX1-Pad1)") (class "Default")
      (node (ref "CX1") (pin "1") (pinfunction "1_1") (pintype "passive"))
      (node (ref "R13") (pin "2") (pinfunction "2_2") (pintype "passive"))
      (node (ref "R14") (pin "1") (pinfunction "1_1") (pintype "passive"))
    )
    (net (code "54") (name "Net-(CX2-Pad1)") (class "Default")
      (node (ref "CX2") (pin "1") (pinfunction "1_1") (pintype "passive"))
      (node (ref "R12") (pin "2") (pinfunction "2_2") (pintype "passive"))
      (node (ref "R18") (pin "1") (pinfunction "1_1") (pintype "passive"))
    )
    (net (code "55") (name "Net-(CX3-Pad1)") (class "Default")
      (node (ref "CX3") (pin "1") (pinfunction "1_1") (pintype "passive"))
      (node (ref "R22") (pin "2") (pinfunction "2_2") (pintype "passive"))
      (node (ref "R23") (pin "1") (pinfunction "1_1") (pintype "passive"))
    )
    (net (code "56") (name "Net-(D2-PadC)") (class "Default")
      (node (ref "D2") (pin "C") (pinfunction "C_C") (pintype "passive"))
      (node (ref "R13") (pin "1") (pinfunction "1_1") (pintype "passive"))
    )
    (net (code "57") (name "Net-(D4-PadC)") (class "Default")
      (node (ref "D4") (pin "C") (pinfunction "C_C") (pintype "passive"))
      (node (ref "R12") (pin "1") (pinfunction "1_1") (pintype "passive"))
    )
    (net (code "58") (name "Net-(D6-PadC)") (class "Default")
      (node (ref "D6") (pin "C") (pinfunction "C_C") (pintype "passive"))
      (node (ref "R22") (pin "1") (pinfunction "1_1") (pintype "passive"))
    )
    (net (code "59") (name "Net-(IR1-OUT)") (class "Default")
      (node (ref "IR1") (pin "1") (pinfunction "OUT_1") (pintype "output"))
      (node (ref "X3") (pin "1") (pinfunction "S_1") (pintype "passive"))
    )
    (net (code "60") (name "Net-(IR1-VCC)") (class "Default")
      (node (ref "IR1") (pin "3") (pinfunction "VCC_3") (pintype "power_in"))
      (node (ref "X3") (pin "3") (pinfunction "S_3") (pintype "passive"))
    )
    (net (code "61") (name "Net-(IR2-OUT)") (class "Default")
      (node (ref "IR2") (pin "1") (pinfunction "OUT_1") (pintype "output"))
      (node (ref "X5") (pin "1") (pinfunction "S_1") (pintype "passive"))
    )
    (net (code "62") (name "Net-(IR2-VCC)") (class "Default")
      (node (ref "IR2") (pin "3") (pinfunction "VCC_3") (pintype "power_in"))
      (node (ref "X5") (pin "3") (pinfunction "S_3") (pintype "passive"))
    )
    (net (code "63") (name "Net-(JP2-PadD+)") (class "Default")
      (node (ref "JP2") (pin "D+") (pinfunction "D+_D+") (pintype "bidirectional"))
      (node (ref "R8") (pin "2") (pinfunction "2_2") (pintype "passive"))
    )
    (net (code "64") (name "Net-(JP2-PadD-)") (class "Default")
      (node (ref "JP2") (pin "D-") (pinfunction "D-_D-") (pintype "bidirectional"))
      (node (ref "R7") (pin "2") (pinfunction "2_2") (pintype "passive"))
    )
    (net (code "65") (name "Net-(LED1-PadA)") (class "Default")
      (node (ref "LED1") (pin "A") (pinfunction "A_A") (pintype "passive"))
      (node (ref "R2") (pin "2") (pinfunction "2_2") (pintype "passive"))
    )
    (net (code "66") (name "Net-(LED2-PadA)") (class "Default")
      (node (ref "LED2") (pin "A") (pinfunction "A_A") (pintype "passive"))
      (node (ref "R3") (pin "1") (pinfunction "1_1") (pintype "passive"))
    )
    (net (code "67") (name "Net-(LED3-PadA)") (class "Default")
      (node (ref "LED3") (pin "A") (pinfunction "A_A") (pintype "passive"))
      (node (ref "R9") (pin "1") (pinfunction "1_1") (pintype "passive"))
    )
    (net (code "68") (name "Net-(LED6-PadA)") (class "Default")
      (node (ref "LED6") (pin "A") (pinfunction "A_A") (pintype "passive"))
      (node (ref "R38") (pin "1") (pinfunction "1_1") (pintype "passive"))
    )
    (net (code "69") (name "Net-(LED7-PadA)") (class "Default")
      (node (ref "LED7") (pin "A") (pinfunction "A_A") (pintype "passive"))
      (node (ref "R41") (pin "1") (pinfunction "1_1") (pintype "passive"))
    )
    (net (code "70") (name "Net-(OK1-A)") (class "Default")
      (node (ref "OK1") (pin "1") (pinfunction "A_1") (pintype "passive"))
      (node (ref "R16") (pin "2") (pinfunction "2_2") (pintype "passive"))
    )
    (net (code "71") (name "Net-(OK1-COL)") (class "Default")
      (node (ref "C11") (pin "+") (pinfunction "+_+") (pintype "passive"))
      (node (ref "D3") (pin "C") (pinfunction "C_C") (pintype "passive"))
      (node (ref "OK1") (pin "5") (pinfunction "COL_5") (pintype "passive"))
      (node (ref "R15") (pin "2") (pinfunction "2_2") (pintype "passive"))
    )
    (net (code "72") (name "Net-(OK1-EMI)") (class "Default")
      (node (ref "OK1") (pin "4") (pinfunction "EMI_4") (pintype "passive"))
      (node (ref "Q2") (pin "1") (pinfunction "G_1") (pintype "passive"))
      (node (ref "R17") (pin "1") (pinfunction "1_1") (pintype "passive"))
    )
    (net (code "73") (name "Net-(OK2-A)") (class "Default")
      (node (ref "OK2") (pin "1") (pinfunction "A_1") (pintype "passive"))
      (node (ref "R20") (pin "2") (pinfunction "2_2") (pintype "passive"))
    )
    (net (code "74") (name "Net-(OK2-COL)") (class "Default")
      (node (ref "C12") (pin "+") (pinfunction "+_+") (pintype "passive"))
      (node (ref "D5") (pin "C") (pinfunction "C_C") (pintype "passive"))
      (node (ref "OK2") (pin "5") (pinfunction "COL_5") (pintype "passive"))
      (node (ref "R19") (pin "2") (pinfunction "2_2") (pintype "passive"))
    )
    (net (code "75") (name "Net-(OK2-EMI)") (class "Default")
      (node (ref "OK2") (pin "4") (pinfunction "EMI_4") (pintype "passive"))
      (node (ref "Q3") (pin "1") (pinfunction "G_1") (pintype "passive"))
      (node (ref "R21") (pin "1") (pinfunction "1_1") (pintype "passive"))
    )
    (net (code "76") (name "Net-(OK3-A)") (class "Default")
      (node (ref "OK3") (pin "1") (pinfunction "A_1") (pintype "passive"))
      (node (ref "R25") (pin "2") (pinfunction "2_2") (pintype "passive"))
    )
    (net (code "77") (name "Net-(OK3-COL)") (class "Default")
      (node (ref "C13") (pin "+") (pinfunction "+_+") (pintype "passive"))
      (node (ref "D7") (pin "C") (pinfunction "C_C") (pintype "passive"))
      (node (ref "OK3") (pin "5") (pinfunction "COL_5") (pintype "passive"))
      (node (ref "R24") (pin "2") (pinfunction "2_2") (pintype "passive"))
    )
    (net (code "78") (name "Net-(OK3-EMI)") (class "Default")
      (node (ref "OK3") (pin "4") (pinfunction "EMI_4") (pintype "passive"))
      (node (ref "Q4") (pin "1") (pinfunction "G_1") (pintype "passive"))
      (node (ref "R26") (pin "1") (pinfunction "1_1") (pintype "passive"))
    )
    (net (code "79") (name "Net-(OK4-A1)") (class "Default")
      (node (ref "OK4") (pin "4") (pinfunction "A1_4") (pintype "passive"))
      (node (ref "T1") (pin "G") (pinfunction "G_G") (pintype "passive"))
    )
    (net (code "80") (name "Net-(OK4-A2)") (class "Default")
      (node (ref "OK4") (pin "6") (pinfunction "A2_6") (pintype "passive"))
      (node (ref "R28") (pin "1") (pinfunction "1_1") (pintype "passive"))
    )
    (net (code "81") (name "Net-(OK5-A1)") (class "Default")
      (node (ref "OK5") (pin "4") (pinfunction "A1_4") (pintype "passive"))
      (node (ref "T2") (pin "G") (pinfunction "G_G") (pintype "passive"))
    )
    (net (code "82") (name "Net-(OK5-A2)") (class "Default")
      (node (ref "OK5") (pin "6") (pinfunction "A2_6") (pintype "passive"))
      (node (ref "R30") (pin "1") (pinfunction "1_1") (pintype "passive"))
    )
    (net (code "83") (name "Net-(OK6-A)") (class "Default")
      (node (ref "OK6") (pin "1") (pinfunction "A_1") (pintype "passive"))
      (node (ref "R31") (pin "2") (pinfunction "2_2") (pintype "passive"))
    )
    (net (code "84") (name "Net-(OK6-A1)") (class "Default")
      (node (ref "OK6") (pin "4") (pinfunction "A1_4") (pintype "passive"))
      (node (ref "T3") (pin "G") (pinfunction "G_G") (pintype "passive"))
    )
    (net (code "85") (name "Net-(OK6-A2)") (class "Default")
      (node (ref "OK6") (pin "6") (pinfunction "A2_6") (pintype "passive"))
      (node (ref "R32") (pin "1") (pinfunction "1_1") (pintype "passive"))
    )
    (net (code "86") (name "Net-(OK7-A1)") (class "Default")
      (node (ref "OK7") (pin "4") (pinfunction "A1_4") (pintype "passive"))
      (node (ref "T4") (pin "G") (pinfunction "G_G") (pintype "passive"))
    )
    (net (code "87") (name "Net-(OK7-A2)") (class "Default")
      (node (ref "OK7") (pin "6") (pinfunction "A2_6") (pintype "passive"))
      (node (ref "R34") (pin "1") (pinfunction "1_1") (pintype "passive"))
    )
    (net (code "88") (name "Net-(OK8-A1)") (class "Default")
      (node (ref "OK8") (pin "4") (pinfunction "A1_4") (pintype "passive"))
      (node (ref "T5") (pin "G") (pinfunction "G_G") (pintype "passive"))
    )
    (net (code "89") (name "Net-(OK8-A2)") (class "Default")
      (node (ref "OK8") (pin "6") (pinfunction "A2_6") (pintype "passive"))
      (node (ref "R36") (pin "1") (pinfunction "1_1") (pintype "passive"))
    )
    (net (code "90") (name "Net-(Q2-D)") (class "Default")
      (node (ref "B1") (pin "+") (pinfunction "+_+") (pintype "passive"))
      (node (ref "D2") (pin "A") (pinfunction "A_A") (pintype "passive"))
      (node (ref "Q2") (pin "2") (pinfunction "D_2") (pintype "passive"))
    )
    (net (code "91") (name "Net-(Q2-S)") (class "Default")
      (node (ref "B1") (pin "-") (pinfunction "-_-") (pintype "passive"))
      (node (ref "C11") (pin "-") (pinfunction "-_-") (pintype "passive"))
      (node (ref "CX1") (pin "2") (pinfunction "2_2") (pintype "passive"))
      (node (ref "D3") (pin "A") (pinfunction "A_A") (pintype "passive"))
      (node (ref "Q2") (pin "3") (pinfunction "S_3") (pintype "passive"))
      (node (ref "R17") (pin "2") (pinfunction "2_2") (pintype "passive"))
    )
    (net (code "92") (name "Net-(Q3-D)") (class "Default")
      (node (ref "B2") (pin "+") (pinfunction "+_+") (pintype "passive"))
      (node (ref "D4") (pin "A") (pinfunction "A_A") (pintype "passive"))
      (node (ref "Q3") (pin "2") (pinfunction "D_2") (pintype "passive"))
    )
    (net (code "93") (name "Net-(Q3-S)") (class "Default")
      (node (ref "B2") (pin "-") (pinfunction "-_-") (pintype "passive"))
      (node (ref "C12") (pin "-") (pinfunction "-_-") (pintype "passive"))
      (node (ref "CX2") (pin "2") (pinfunction "2_2") (pintype "passive"))
      (node (ref "D5") (pin "A") (pinfunction "A_A") (pintype "passive"))
      (node (ref "Q3") (pin "3") (pinfunction "S_3") (pintype "passive"))
      (node (ref "R21") (pin "2") (pinfunction "2_2") (pintype "passive"))
    )
    (net (code "94") (name "Net-(Q4-D)") (class "Default")
      (node (ref "B3") (pin "+") (pinfunction "+_+") (pintype "passive"))
      (node (ref "D6") (pin "A") (pinfunction "A_A") (pintype "passive"))
      (node (ref "Q4") (pin "2") (pinfunction "D_2") (pintype "passive"))
    )
    (net (code "95") (name "Net-(Q4-S)") (class "Default")
      (node (ref "B3") (pin "-") (pinfunction "-_-") (pintype "passive"))
      (node (ref "C13") (pin "-") (pinfunction "-_-") (pintype "passive"))
      (node (ref "CX3") (pin "2") (pinfunction "2_2") (pintype "passive"))
      (node (ref "D7") (pin "A") (pinfunction "A_A") (pintype "passive"))
      (node (ref "Q4") (pin "3") (pinfunction "S_3") (pintype "passive"))
      (node (ref "R26") (pin "2") (pinfunction "2_2") (pintype "passive"))
    )
    (net (code "96") (name "Net-(R4-Pad2)") (class "Default")
      (node (ref "R4") (pin "2") (pinfunction "2_2") (pintype "passive"))
      (node (ref "U$3") (pin "UART_TX") (pinfunction "UART_TX_UART_TX") (pintype "bidirectional"))
    )
    (net (code "97") (name "Net-(R5-Pad2)") (class "Default")
      (node (ref "R5") (pin "2") (pinfunction "2_2") (pintype "passive"))
      (node (ref "U$3") (pin "UART_RX") (pinfunction "UART_RX_UART_RX") (pintype "bidirectional"))
    )
    (net (code "98") (name "Net-(R14-Pad2)") (class "Default")
      (node (ref "R14") (pin "2") (pinfunction "2_2") (pintype "passive"))
      (node (ref "R15") (pin "1") (pinfunction "1_1") (pintype "passive"))
    )
    (net (code "99") (name "Net-(R18-Pad2)") (class "Default")
      (node (ref "R18") (pin "2") (pinfunction "2_2") (pintype "passive"))
      (node (ref "R19") (pin "1") (pinfunction "1_1") (pintype "passive"))
    )
    (net (code "100") (name "Net-(R23-Pad2)") (class "Default")
      (node (ref "R23") (pin "2") (pinfunction "2_2") (pintype "passive"))
      (node (ref "R24") (pin "1") (pinfunction "1_1") (pintype "passive"))
    )
    (net (code "101") (name "Net-(R38-Pad2)") (class "Default")
      (node (ref "R38") (pin "2") (pinfunction "2_2") (pintype "passive"))
      (node (ref "U$1") (pin "PIO1") (pinfunction "PIO1_PIO1") (pintype "bidirectional"))
    )
    (net (code "102") (name "Net-(R39-Pad2)") (class "Default")
      (node (ref "R39") (pin "2") (pinfunction "2_2") (pintype "passive"))
      (node (ref "U$1") (pin "UART_TX") (pinfunction "UART_TX_UART_TX") (pintype "bidirectional"))
    )
    (net (code "103") (name "Net-(R40-Pad2)") (class "Default")
      (node (ref "R40") (pin "2") (pinfunction "2_2") (pintype "passive"))
      (node (ref "U$1") (pin "UART_RX") (pinfunction "UART_RX_UART_RX") (pintype "bidirectional"))
    )
    (net (code "104") (name "Net-(R41-Pad2)") (class "Default")
      (node (ref "R41") (pin "2") (pinfunction "2_2") (pintype "passive"))
      (node (ref "U$11") (pin "PIO1") (pinfunction "PIO1_PIO1") (pintype "bidirectional"))
    )
    (net (code "105") (name "Net-(R42-Pad2)") (class "Default")
      (node (ref "R42") (pin "2") (pinfunction "2_2") (pintype "passive"))
      (node (ref "U$11") (pin "UART_TX") (pinfunction "UART_TX_UART_TX") (pintype "bidirectional"))
    )
    (net (code "106") (name "Net-(R43-Pad2)") (class "Default")
      (node (ref "R43") (pin "2") (pinfunction "2_2") (pintype "passive"))
      (node (ref "U$11") (pin "UART_RX") (pinfunction "UART_RX_UART_RX") (pintype "bidirectional"))
    )
    (net (code "107") (name "Net-(T1-A1)") (class "Default")
      (node (ref "C14") (pin "1") (pinfunction "1_1") (pintype "passive"))
      (node (ref "T1") (pin "T1") (pinfunction "A1_T1") (pintype "passive"))
      (node (ref "U$4") (pin "2") (pinfunction "2_2") (pintype "passive"))
    )
    (net (code "108") (name "Net-(T2-A1)") (class "Default")
      (node (ref "C15") (pin "1") (pinfunction "1_1") (pintype "passive"))
      (node (ref "T2") (pin "T1") (pinfunction "A1_T1") (pintype "passive"))
      (node (ref "U$6") (pin "2") (pinfunction "2_2") (pintype "passive"))
    )
    (net (code "109") (name "Net-(T3-A1)") (class "Default")
      (node (ref "C16") (pin "1") (pinfunction "1_1") (pintype "passive"))
      (node (ref "C17") (pin "1") (pinfunction "1_1") (pintype "passive"))
      (node (ref "T3") (pin "T1") (pinfunction "A1_T1") (pintype "passive"))
      (node (ref "U$8") (pin "2") (pinfunction "2_2") (pintype "passive"))
    )
    (net (code "110") (name "Net-(X1A-S)") (class "Default")
      (node (ref "U$1") (pin "VCC") (pinfunction "VCC_VCC") (pintype "bidirectional"))
      (node (ref "X1") (pin "1") (pinfunction "S_1") (pintype "passive"))
    )
    (net (code "111") (name "Net-(X1C-S)") (class "Default")
      (node (ref "R39") (pin "1") (pinfunction "1_1") (pintype "passive"))
      (node (ref "X1") (pin "3") (pinfunction "S_3") (pintype "passive"))
    )
    (net (code "112") (name "Net-(X1D-S)") (class "Default")
      (node (ref "R40") (pin "1") (pinfunction "1_1") (pintype "passive"))
      (node (ref "X1") (pin "4") (pinfunction "S_4") (pintype "passive"))
    )
    (net (code "113") (name "Net-(X1E-S)") (class "Default")
      (node (ref "U$1") (pin "UART_RTS") (pinfunction "UART_RTS_UART_RTS") (pintype "bidirectional"))
      (node (ref "X1") (pin "5") (pinfunction "S_5") (pintype "passive"))
    )
    (net (code "114") (name "Net-(X4A-S)") (class "Default")
      (node (ref "U$11") (pin "VCC") (pinfunction "VCC_VCC") (pintype "bidirectional"))
      (node (ref "X4") (pin "1") (pinfunction "S_1") (pintype "passive"))
    )
    (net (code "115") (name "Net-(X4C-S)") (class "Default")
      (node (ref "R42") (pin "1") (pinfunction "1_1") (pintype "passive"))
      (node (ref "X4") (pin "3") (pinfunction "S_3") (pintype "passive"))
    )
    (net (code "116") (name "Net-(X4D-S)") (class "Default")
      (node (ref "R43") (pin "1") (pinfunction "1_1") (pintype "passive"))
      (node (ref "X4") (pin "4") (pinfunction "S_4") (pintype "passive"))
    )
    (net (code "117") (name "Net-(X4E-S)") (class "Default")
      (node (ref "U$11") (pin "UART_RTS") (pinfunction "UART_RTS_UART_RTS") (pintype "bidirectional"))
      (node (ref "X4") (pin "5") (pinfunction "S_5") (pintype "passive"))
    )
    (net (code "118") (name "unconnected-(ATMEGA32U4-PE6-Pad1)") (class "Default")
      (node (ref "ATMEGA32U4") (pin "1") (pinfunction "PE6_1") (pintype "bidirectional"))
    )
    (net (code "119") (name "unconnected-(ATMEGA32U4-PF7(ADC7)-Pad36)") (class "Default")
      (node (ref "ATMEGA32U4") (pin "36") (pinfunction "PF7(ADC7)_36") (pintype "bidirectional"))
    )
    (net (code "120") (name "unconnected-(JP3-PadD+)") (class "Default")
      (node (ref "JP3") (pin "D+") (pinfunction "D+_D+") (pintype "bidirectional"))
    )
    (net (code "121") (name "unconnected-(JP3-PadD-)") (class "Default")
      (node (ref "JP3") (pin "D-") (pinfunction "D-_D-") (pintype "bidirectional"))
    )
    (net (code "122") (name "unconnected-(OK1-BAS-Pad6)") (class "Default")
      (node (ref "OK1") (pin "6") (pinfunction "BAS_6") (pintype "passive"))
    )
    (net (code "123") (name "unconnected-(OK2-BAS-Pad6)") (class "Default")
      (node (ref "OK2") (pin "6") (pinfunction "BAS_6") (pintype "passive"))
    )
    (net (code "124") (name "unconnected-(OK3-BAS-Pad6)") (class "Default")
      (node (ref "OK3") (pin "6") (pinfunction "BAS_6") (pintype "passive"))
    )
    (net (code "125") (name "unconnected-(PWRC-S-Pad3)") (class "Default")
      (node (ref "PWR") (pin "3") (pinfunction "S_3") (pintype "passive"))
    )
    (net (code "126") (name "unconnected-(U$1-PadNC1)") (class "Default")
      (node (ref "U$1") (pin "NC1") (pinfunction "NC1_NC1") (pintype "bidirectional"))
    )
    (net (code "127") (name "unconnected-(U$1-PadNC2)") (class "Default")
      (node (ref "U$1") (pin "NC2") (pinfunction "NC2_NC2") (pintype "bidirectional"))
    )
    (net (code "128") (name "unconnected-(U$1-PadNC3)") (class "Default")
      (node (ref "U$1") (pin "NC3") (pinfunction "NC3_NC3") (pintype "bidirectional"))
    )
    (net (code "129") (name "unconnected-(U$1-PadNV1)") (class "Default")
      (node (ref "U$1") (pin "NV1") (pinfunction "NV1_NV1") (pintype "bidirectional"))
    )
    (net (code "130") (name "unconnected-(U$1-PadNV2)") (class "Default")
      (node (ref "U$1") (pin "NV2") (pinfunction "NV2_NV2") (pintype "bidirectional"))
    )
    (net (code "131") (name "unconnected-(U$1-PadPIO0)") (class "Default")
      (node (ref "U$1") (pin "PIO0") (pinfunction "PIO0_PIO0") (pintype "bidirectional"))
    )
    (net (code "132") (name "unconnected-(U$1-PadPIO2)") (class "Default")
      (node (ref "U$1") (pin "PIO2") (pinfunction "PIO2_PIO2") (pintype "bidirectional"))
    )
    (net (code "133") (name "unconnected-(U$1-PadPIO3)") (class "Default")
      (node (ref "U$1") (pin "PIO3") (pinfunction "PIO3_PIO3") (pintype "bidirectional"))
    )
    (net (code "134") (name "unconnected-(U$1-PadRESETB)") (class "Default")
      (node (ref "U$1") (pin "RESETB") (pinfunction "RESETB_RESETB") (pintype "bidirectional"))
    )
    (net (code "135") (name "unconnected-(U$1-PadUART_CTS)") (class "Default")
      (node (ref "U$1") (pin "UART_CTS") (pinfunction "UART_CTS_UART_CTS") (pintype "bidirectional"))
    )
    (net (code "136") (name "unconnected-(U$3-PadNC1)") (class "Default")
      (node (ref "U$3") (pin "NC1") (pinfunction "NC1_NC1") (pintype "bidirectional"))
    )
    (net (code "137") (name "unconnected-(U$3-PadNC2)") (class "Default")
      (node (ref "U$3") (pin "NC2") (pinfunction "NC2_NC2") (pintype "bidirectional"))
    )
    (net (code "138") (name "unconnected-(U$3-PadNC3)") (class "Default")
      (node (ref "U$3") (pin "NC3") (pinfunction "NC3_NC3") (pintype "bidirectional"))
    )
    (net (code "139") (name "unconnected-(U$3-PadNV1)") (class "Default")
      (node (ref "U$3") (pin "NV1") (pinfunction "NV1_NV1") (pintype "bidirectional"))
    )
    (net (code "140") (name "unconnected-(U$3-PadNV2)") (class "Default")
      (node (ref "U$3") (pin "NV2") (pinfunction "NV2_NV2") (pintype "bidirectional"))
    )
    (net (code "141") (name "unconnected-(U$3-PadPIO0)") (class "Default")
      (node (ref "U$3") (pin "PIO0") (pinfunction "PIO0_PIO0") (pintype "bidirectional"))
    )
    (net (code "142") (name "unconnected-(U$3-PadPIO2)") (class "Default")
      (node (ref "U$3") (pin "PIO2") (pinfunction "PIO2_PIO2") (pintype "bidirectional"))
    )
    (net (code "143") (name "unconnected-(U$3-PadPIO3)") (class "Default")
      (node (ref "U$3") (pin "PIO3") (pinfunction "PIO3_PIO3") (pintype "bidirectional"))
    )
    (net (code "144") (name "unconnected-(U$3-PadRESETB)") (class "Default")
      (node (ref "U$3") (pin "RESETB") (pinfunction "RESETB_RESETB") (pintype "bidirectional"))
    )
    (net (code "145") (name "unconnected-(U$3-PadUART_CTS)") (class "Default")
      (node (ref "U$3") (pin "UART_CTS") (pinfunction "UART_CTS_UART_CTS") (pintype "bidirectional"))
    )
    (net (code "146") (name "unconnected-(U$11-PadNC1)") (class "Default")
      (node (ref "U$11") (pin "NC1") (pinfunction "NC1_NC1") (pintype "bidirectional"))
    )
    (net (code "147") (name "unconnected-(U$11-PadNC2)") (class "Default")
      (node (ref "U$11") (pin "NC2") (pinfunction "NC2_NC2") (pintype "bidirectional"))
    )
    (net (code "148") (name "unconnected-(U$11-PadNC3)") (class "Default")
      (node (ref "U$11") (pin "NC3") (pinfunction "NC3_NC3") (pintype "bidirectional"))
    )
    (net (code "149") (name "unconnected-(U$11-PadNV1)") (class "Default")
      (node (ref "U$11") (pin "NV1") (pinfunction "NV1_NV1") (pintype "bidirectional"))
    )
    (net (code "150") (name "unconnected-(U$11-PadNV2)") (class "Default")
      (node (ref "U$11") (pin "NV2") (pinfunction "NV2_NV2") (pintype "bidirectional"))
    )
    (net (code "151") (name "unconnected-(U$11-PadPIO0)") (class "Default")
      (node (ref "U$11") (pin "PIO0") (pinfunction "PIO0_PIO0") (pintype "bidirectional"))
    )
    (net (code "152") (name "unconnected-(U$11-PadPIO2)") (class "Default")
      (node (ref "U$11") (pin "PIO2") (pinfunction "PIO2_PIO2") (pintype "bidirectional"))
    )
    (net (code "153") (name "unconnected-(U$11-PadPIO3)") (class "Default")
      (node (ref "U$11") (pin "PIO3") (pinfunction "PIO3_PIO3") (pintype "bidirectional"))
    )
    (net (code "154") (name "unconnected-(U$11-PadRESETB)") (class "Default")
      (node (ref "U$11") (pin "RESETB") (pinfunction "RESETB_RESETB") (pintype "bidirectional"))
    )
    (net (code "155") (name "unconnected-(U$11-PadUART_CTS)") (class "Default")
      (node (ref "U$11") (pin "UART_CTS") (pinfunction "UART_CTS_UART_CTS") (pintype "bidirectional"))
    )
  )
)
